# Optic_sensor.net
KiCad netlist of a schematic drawn in Altium Designer
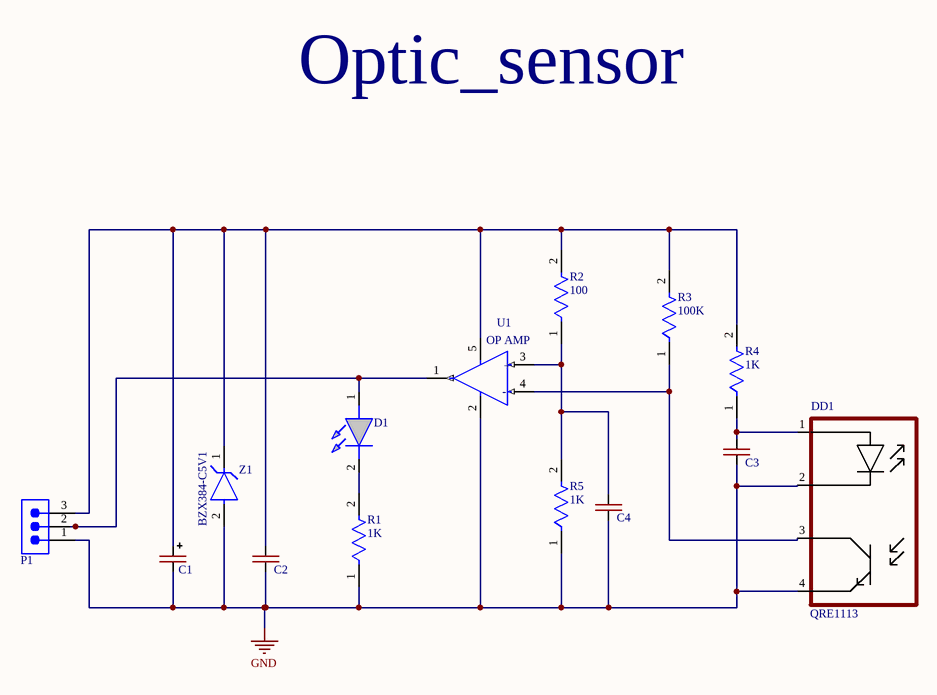
[diagram p0: Optic_sensor.SchDoc]

(export (version "E")
  (design (tool "Eeschema 10.0.6"))
  (components
    (comp (ref "C1")
      (value "CAP-POLAR")
      (footprint "CAP-TAN-C")
      (libsource (lib "PASSIVE_COMPONENTS") (part "CAP-POLAR"))
    )
    (comp (ref "C2")
      (value "CAP-NON-POLAR")
      (footprint "CAP-0805")
      (libsource (lib "PASSIVE_COMPONENTS") (part "CAP-NON-POLAR"))
    )
    (comp (ref "C3")
      (value "CAP-NON-POLAR")
      (footprint "CAP-0805")
      (libsource (lib "PASSIVE_COMPONENTS") (part "CAP-NON-POLAR"))
    )
    (comp (ref "C4")
      (value "CAP-NON-POLAR")
      (footprint "CAP-0805")
      (libsource (lib "PASSIVE_COMPONENTS") (part "CAP-NON-POLAR"))
    )
    (comp (ref "D1")
      (value "151031YS06000")
      (footprint "LED_RED")
      (description "WURTH ELEKTRONIK - 151031YS06000 - LED, Yellow, Through Hole, T-1 (3mm), 30 mA, 2 V, 590 nm")
      (fields (field (name "MOUSER PART NUMBER") "710-151031YS06000"))
      (libsource (lib "Optic-LED") (part "LED"))
    )
    (comp (ref "DD1") (value "QRE1113") (footprint "QRE1113") (libsource (lib "QRE1113") (part "QRE1113")))
    (comp (ref "P1")
      (value "61900311121")
      (footprint "61900311121")
      (description "WR-WTB THT Male Vertical Locking Header, pitch 2.54mm, 3pins")
      (fields (field (name "MANUFACTURER") "Wurth Elektronik"))
      (libsource (lib "Altium_WR-WTB (rev22b)") (part "61900311121"))
    )
    (comp (ref "R1")
      (value "1K")
      (footprint "RES-0805")
      (libsource (lib "PASSIVE_COMPONENTS") (part "RES-CONST"))
    )
    (comp (ref "R2")
      (value "100")
      (footprint "RES-0805")
      (libsource (lib "PASSIVE_COMPONENTS") (part "RES-CONST"))
    )
    (comp (ref "R3")
      (value "100K")
      (footprint "RES-0805")
      (libsource (lib "PASSIVE_COMPONENTS") (part "RES-CONST"))
    )
    (comp (ref "R4")
      (value "1K")
      (footprint "RES-0805")
      (libsource (lib "PASSIVE_COMPONENTS") (part "RES-CONST"))
    )
    (comp (ref "R5")
      (value "1K")
      (footprint "RES-0805")
      (libsource (lib "PASSIVE_COMPONENTS") (part "RES-CONST"))
    )
    (comp (ref "U1")
      (value "OP AMP")
      (footprint "SOT-23-5")
      (libsource (lib "Integrated_Circuts") (part "MCP6001T"))
    )
    (comp (ref "Z1")
      (value "BZX384-C5V1")
      (footprint "BZX384-SOD323-IPC_C")
      (libsource (lib "Diodes") (part "BZX384-C5V1"))
    )
  )
  (nets
    (net (code "1") (name "GND") (class "Default")
      (node (ref "C1") (pin "2") (pinfunction "-_2") (pintype "passive"))
      (node (ref "C2") (pin "1") (pinfunction "1_1") (pintype "passive"))
      (node (ref "C3") (pin "1") (pinfunction "1_1") (pintype "passive"))
      (node (ref "C4") (pin "1") (pinfunction "1_1") (pintype "passive"))
      (node (ref "DD1") (pin "2") (pinfunction "CATHODE_2") (pintype "passive"))
      (node (ref "DD1") (pin "4") (pintype "passive"))
      (node (ref "P1") (pin "1") (pinfunction "1_1") (pintype "passive"))
      (node (ref "R1") (pin "1") (pinfunction "1_1") (pintype "passive"))
      (node (ref "R5") (pin "1") (pinfunction "1_1") (pintype "passive"))
      (node (ref "U1") (pin "2") (pinfunction "VSS_2") (pintype "power_in"))
      (node (ref "Z1") (pin "2") (pinfunction "A_2") (pintype "passive"))
    )
    (net (code "2") (name "Net-(C1-+)") (class "Default")
      (node (ref "C1") (pin "1") (pinfunction "+_1") (pintype "passive"))
      (node (ref "C2") (pin "2") (pinfunction "2_2") (pintype "passive"))
      (node (ref "P1") (pin "3") (pinfunction "3_3") (pintype "passive"))
      (node (ref "R2") (pin "2") (pinfunction "2_2") (pintype "passive"))
      (node (ref "R3") (pin "2") (pinfunction "2_2") (pintype "passive"))
      (node (ref "R4") (pin "2") (pinfunction "2_2") (pintype "passive"))
      (node (ref "U1") (pin "5") (pinfunction "VDD_5") (pintype "power_in"))
      (node (ref "Z1") (pin "1") (pinfunction "C_1") (pintype "passive"))
    )
    (net (code "3") (name "Net-(D1-A)") (class "Default")
      (node (ref "D1") (pin "1") (pinfunction "A_1") (pintype "passive"))
      (node (ref "P1") (pin "2") (pinfunction "2_2") (pintype "passive"))
      (node (ref "U1") (pin "1") (pinfunction "VOUT_1") (pintype "output"))
    )
    (net (code "4") (name "Net-(D1-K)") (class "Default")
      (node (ref "D1") (pin "2") (pinfunction "K_2") (pintype "passive"))
      (node (ref "R1") (pin "2") (pinfunction "2_2") (pintype "passive"))
    )
    (net (code "5") (name "Net-(DD1-ANODE)") (class "Default")
      (node (ref "C3") (pin "2") (pinfunction "2_2") (pintype "passive"))
      (node (ref "DD1") (pin "1") (pinfunction "ANODE_1") (pintype "passive"))
      (node (ref "R4") (pin "1") (pinfunction "1_1") (pintype "passive"))
    )
    (net (code "6") (name "Net-(U1-VIN+)") (class "Default")
      (node (ref "C4") (pin "2") (pinfunction "2_2") (pintype "passive"))
      (node (ref "R2") (pin "1") (pinfunction "1_1") (pintype "passive"))
      (node (ref "R5") (pin "2") (pinfunction "2_2") (pintype "passive"))
      (node (ref "U1") (pin "3") (pinfunction "VIN+_3") (pintype "input"))
    )
    (net (code "7") (name "Net-(U1-VIN-)") (class "Default")
      (node (ref "DD1") (pin "3") (pintype "passive"))
      (node (ref "R3") (pin "1") (pinfunction "1_1") (pintype "passive"))
      (node (ref "U1") (pin "4") (pinfunction "VIN-_4") (pintype "input"))
    )
  )
)
